# Schematic.net
KiCad netlist of a schematic drawn in Altium Designer
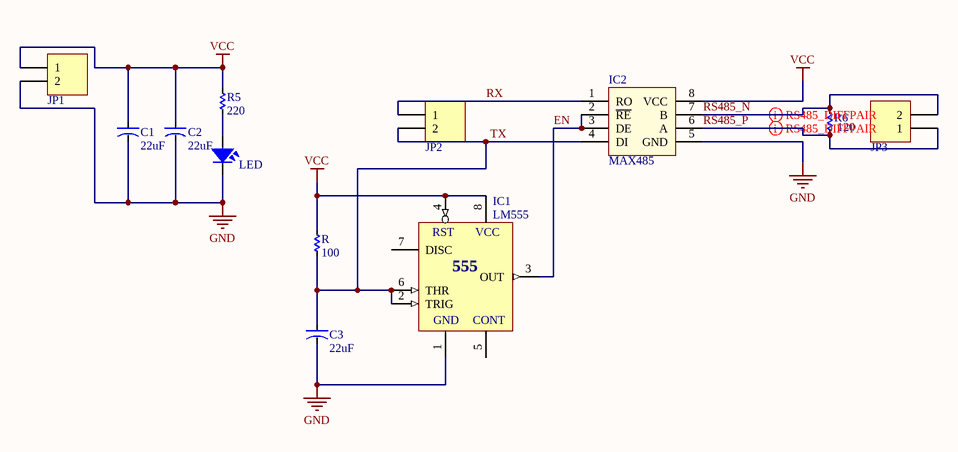
[diagram p0: Schematic.SchDoc]

(export (version "E")
  (design (tool "Eeschema 10.0.6"))
  (components
    (comp (ref "C1")
      (value "22uF")
      (footprint "CA-ALU-2.54")
      (description "Capacitor (Semiconductor SIM Model)")
      (fields (field (name "PUBLISHER") "Altium Limited"))
      (libsource (lib "LIBRARYALT") (part "CN-ALU-DIP"))
    )
    (comp (ref "C2")
      (value "22uF")
      (footprint "CA-ALU-2.54")
      (description "Capacitor (Semiconductor SIM Model)")
      (fields (field (name "PUBLISHER") "Altium Limited"))
      (libsource (lib "LIBRARYALT") (part "CN-ALU-DIP"))
    )
    (comp (ref "C3")
      (value "22uF")
      (footprint "CA-ALU-2.54")
      (description "Capacitor (Semiconductor SIM Model)")
      (fields (field (name "PUBLISHER") "Altium Limited"))
      (libsource (lib "LIBRARYALT") (part "CN-ALU-DIP"))
    )
    (comp (ref "IC1")
      (value "LM555")
      (footprint "DIP8")
      (description "Timer")
      (libsource (lib "LIBRARYALT") (part "LM555"))
    )
    (comp (ref "IC2")
      (value "MAX485")
      (footprint "DIP8/W0.3")
      (description "RS232 - RS485 (Same sn75176)")
      (libsource (lib "echipkool-com-library") (part "MAX485"))
    )
    (comp (ref "JP1")
      (value "Header 2_1")
      (footprint "HED2")
      (description "Header, 2-Pin")
      (fields (field (name "MANUFACTURER") "Generic Components"))
      (libsource (lib "") (part "Header 2_1_1"))
    )
    (comp (ref "JP2")
      (value "Header 2_1")
      (footprint "HED2")
      (description "Header, 2-Pin")
      (fields (field (name "MANUFACTURER") "Generic Components"))
      (libsource (lib "") (part "Header 2_1_1"))
    )
    (comp (ref "JP3")
      (value "Header 2_1")
      (footprint "HED2")
      (description "Header, 2-Pin")
      (fields (field (name "MANUFACTURER") "Generic Components"))
      (libsource (lib "echipkool-com-library") (part "Header 2_1"))
    )
    (comp (ref "LED")
      (value "LED")
      (footprint "LED-5-Green")
      (description "LED Single colour Green and Red")
      (libsource (lib "echipkool-com-library") (part "LED"))
    )
    (comp (ref "R")
      (value "100")
      (footprint "RES-1/4W")
      (description "Res")
      (fields
        (field (name "MANUFACTURER") "Generic Components")
        (field (name "PUBLISHER") "Altium Hobart Technology Centre")
      )
      (libsource (lib "LIBRARYALT") (part "Res"))
    )
    (comp (ref "R5")
      (value "220")
      (footprint "RES-1/4W")
      (description "Res")
      (fields
        (field (name "MANUFACTURER") "Generic Components")
        (field (name "PUBLISHER") "Altium Hobart Technology Centre")
      )
      (libsource (lib "LIBRARYALT") (part "Res"))
    )
    (comp (ref "R6")
      (value "120")
      (footprint "RES-1/4W")
      (description "Res")
      (fields
        (field (name "MANUFACTURER") "Generic Components")
        (field (name "PUBLISHER") "Altium Hobart Technology Centre")
      )
      (libsource (lib "LIBRARYALT") (part "Res"))
    )
  )
  (nets
    (net (code "1") (name "/EN") (class "Default")
      (node (ref "IC1") (pin "3") (pinfunction "OUT_3") (pintype "output"))
      (node (ref "IC2") (pin "2") (pinfunction "~{RE}_2") (pintype "passive"))
      (node (ref "IC2") (pin "3") (pinfunction "DE_3") (pintype "passive"))
    )
    (net (code "2") (name "/RS485_N") (class "Default")
      (node (ref "IC2") (pin "7") (pinfunction "B_7") (pintype "passive"))
      (node (ref "JP3") (pin "2") (pinfunction "2_2") (pintype "passive"))
      (node (ref "R6") (pin "1") (pinfunction "1_1") (pintype "passive"))
    )
    (net (code "3") (name "/RS485_P") (class "Default")
      (node (ref "IC2") (pin "6") (pinfunction "A_6") (pintype "passive"))
      (node (ref "JP3") (pin "1") (pinfunction "1_1") (pintype "passive"))
      (node (ref "R6") (pin "2") (pinfunction "2_2") (pintype "passive"))
    )
    (net (code "4") (name "/RX") (class "Default")
      (node (ref "IC2") (pin "1") (pinfunction "RO_1") (pintype "passive"))
      (node (ref "JP2") (pin "1") (pinfunction "1_1") (pintype "passive"))
    )
    (net (code "5") (name "/TX") (class "Default")
      (node (ref "C3") (pin "1") (pinfunction "1_1") (pintype "passive"))
      (node (ref "IC1") (pin "2") (pinfunction "TRIG_2") (pintype "input"))
      (node (ref "IC1") (pin "6") (pinfunction "THR_6") (pintype "input"))
      (node (ref "IC2") (pin "4") (pinfunction "DI_4") (pintype "passive"))
      (node (ref "JP2") (pin "2") (pinfunction "2_2") (pintype "passive"))
      (node (ref "R") (pin "2") (pinfunction "2_2") (pintype "passive"))
    )
    (net (code "6") (name "GND") (class "Default")
      (node (ref "C1") (pin "2") (pinfunction "2_2") (pintype "passive"))
      (node (ref "C2") (pin "2") (pinfunction "2_2") (pintype "passive"))
      (node (ref "C3") (pin "2") (pinfunction "2_2") (pintype "passive"))
      (node (ref "IC1") (pin "1") (pinfunction "GND_1") (pintype "power_in"))
      (node (ref "IC2") (pin "5") (pinfunction "GND_5") (pintype "passive"))
      (node (ref "JP1") (pin "2") (pinfunction "2_2") (pintype "passive"))
      (node (ref "LED") (pin "2") (pinfunction "2_2") (pintype "passive"))
    )
    (net (code "7") (name "Net-(LED-Pad1)") (class "Default")
      (node (ref "LED") (pin "1") (pinfunction "1_1") (pintype "passive"))
      (node (ref "R5") (pin "2") (pinfunction "2_2") (pintype "passive"))
    )
    (net (code "8") (name "VCC") (class "Default")
      (node (ref "C1") (pin "1") (pinfunction "1_1") (pintype "passive"))
      (node (ref "C2") (pin "1") (pinfunction "1_1") (pintype "passive"))
      (node (ref "IC1") (pin "4") (pinfunction "RST_4") (pintype "input"))
      (node (ref "IC1") (pin "8") (pinfunction "VCC_8") (pintype "power_in"))
      (node (ref "IC2") (pin "8") (pinfunction "VCC_8") (pintype "passive"))
      (node (ref "JP1") (pin "1") (pinfunction "1_1") (pintype "passive"))
      (node (ref "R") (pin "1") (pinfunction "1_1") (pintype "passive"))
      (node (ref "R5") (pin "1") (pinfunction "1_1") (pintype "passive"))
    )
    (net (code "9") (name "unconnected-(IC1-CONT-Pad5)") (class "Default")
      (node (ref "IC1") (pin "5") (pinfunction "CONT_5") (pintype "passive"))
    )
    (net (code "10") (name "unconnected-(IC1-DISC-Pad7)") (class "Default")
      (node (ref "IC1") (pin "7") (pinfunction "DISC_7") (pintype "open_collector"))
    )
  )
)
